# 05-Power_A.net
KiCad netlist of a schematic drawn in Altium Designer
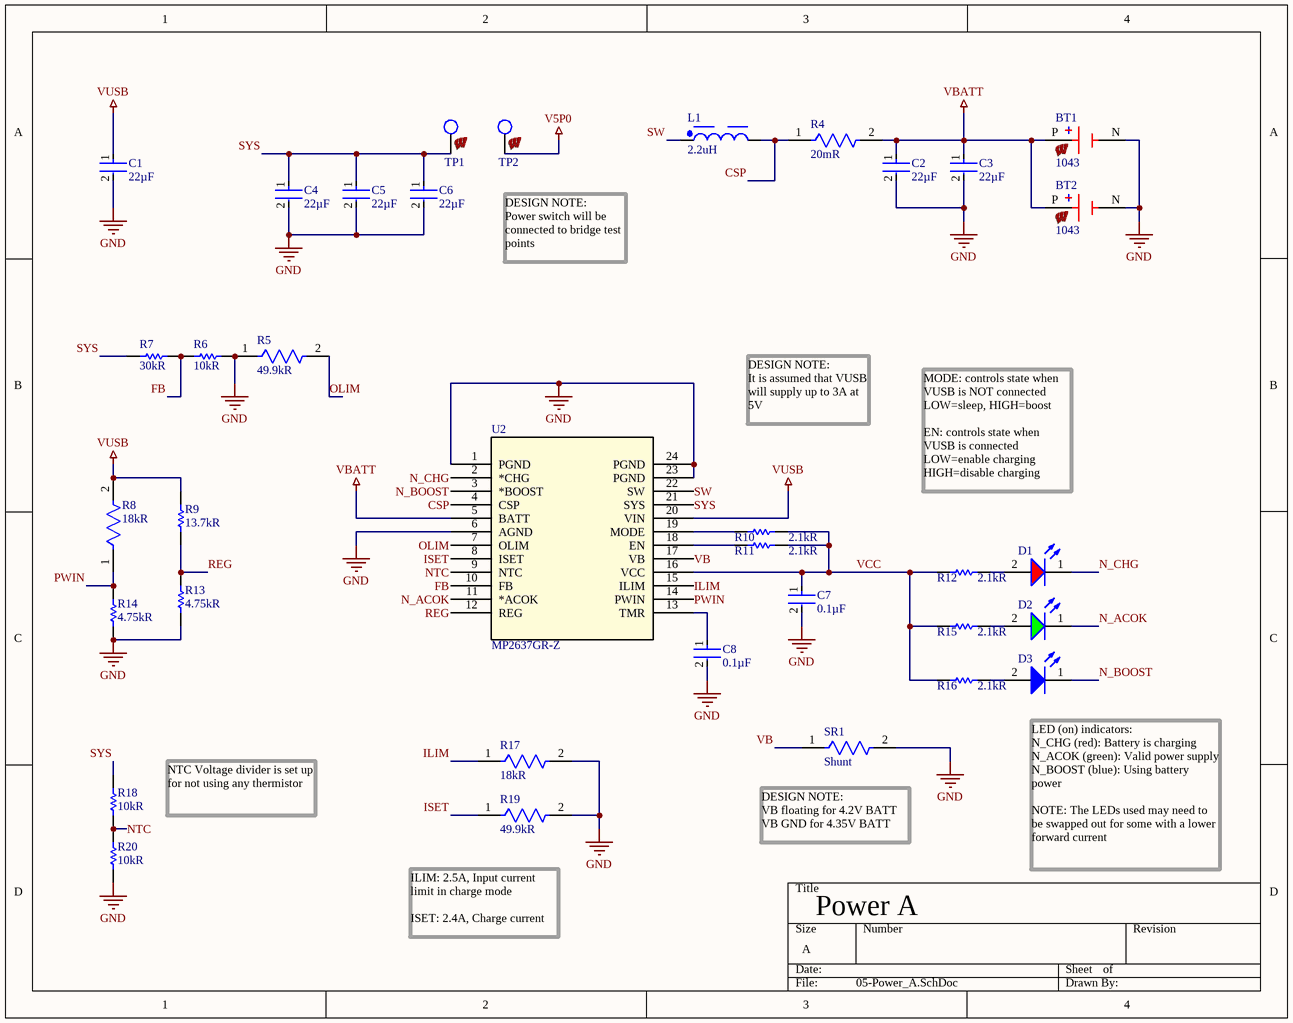
[diagram p0: 05-Power_A.SchDoc]

(export (version "E")
  (design (tool "Eeschema 10.0.6"))
  (components
    (comp (ref "BT1")
      (value "1043")
      (footprint "BAT_1043")
      (fields (field (name "MANUFACTURER") "Keystone Electronics"))
      (libsource (lib "uw-madison-parts") (part "1043"))
    )
    (comp (ref "BT2")
      (value "1043")
      (footprint "BAT_1043")
      (fields (field (name "MANUFACTURER") "Keystone Electronics"))
      (libsource (lib "uw-madison-parts") (part "1043"))
    )
    (comp (ref "C1")
      (value "22µF")
      (footprint "FP-GRM21B-0_2-e0_2_0_7-IPC_B")
      (description "Chip Multilayer Ceramic Capacitors for General Purpose, 0805, 22uF, X7R, 15%, 20%, 10V")
      (libsource (lib "Altium Content Vault") (part "b4654b650e69147ec39a6b967a45e02"))
    )
    (comp (ref "C2")
      (value "22µF")
      (footprint "FP-GRM21B-0_2-e0_2_0_7-IPC_B")
      (description "Chip Multilayer Ceramic Capacitors for General Purpose, 0805, 22uF, X7R, 15%, 20%, 10V")
      (libsource (lib "Altium Content Vault") (part "b4654b650e69147ec39a6b967a45e02"))
    )
    (comp (ref "C3")
      (value "22µF")
      (footprint "FP-GRM21B-0_2-e0_2_0_7-IPC_B")
      (description "Chip Multilayer Ceramic Capacitors for General Purpose, 0805, 22uF, X7R, 15%, 20%, 10V")
      (libsource (lib "Altium Content Vault") (part "b4654b650e69147ec39a6b967a45e02"))
    )
    (comp (ref "C4")
      (value "22µF")
      (footprint "FP-GRM21B-0_2-e0_2_0_7-IPC_B")
      (description "Chip Multilayer Ceramic Capacitors for General Purpose, 0805, 22uF, X7R, 15%, 20%, 10V")
      (libsource (lib "Altium Content Vault") (part "b4654b650e69147ec39a6b967a45e02"))
    )
    (comp (ref "C5")
      (value "22µF")
      (footprint "FP-GRM21B-0_2-e0_2_0_7-IPC_B")
      (description "Chip Multilayer Ceramic Capacitors for General Purpose, 0805, 22uF, X7R, 15%, 20%, 10V")
      (libsource (lib "Altium Content Vault") (part "b4654b650e69147ec39a6b967a45e02"))
    )
    (comp (ref "C6")
      (value "22µF")
      (footprint "FP-GRM21B-0_2-e0_2_0_7-IPC_B")
      (description "Chip Multilayer Ceramic Capacitors for General Purpose, 0805, 22uF, X7R, 15%, 20%, 10V")
      (libsource (lib "Altium Content Vault") (part "b4654b650e69147ec39a6b967a45e02"))
    )
    (comp (ref "C7")
      (value "0.1µF")
      (footprint "FP-C0805C-DN-MFG")
      (description "CAP CER 0.1UF 50V X7R 0805")
      (fields
        (field (name "MANUFACTURER PART NUMBER") "C0805C104K5RACTU")
        (field (name "MANUFACTURER") "KEMET")
      )
      (libsource (lib "Altium Content Vault") (part "b4654b650e69147ec39a6b967a45e02"))
    )
    (comp (ref "C8")
      (value "0.1µF")
      (footprint "FP-C0805C-DN-MFG")
      (description "CAP CER 0.1UF 50V X7R 0805")
      (fields
        (field (name "MANUFACTURER PART NUMBER") "C0805C104K5RACTU")
        (field (name "MANUFACTURER") "KEMET")
      )
      (libsource (lib "Altium Content Vault") (part "b4654b650e69147ec39a6b967a45e02"))
    )
    (comp (ref "D1")
      (value "150080RS75000")
      (footprint "WL-SMCW_0805_150080xx75000")
      (description "150080RS75000\r\nLED Uni-Color Red 630nm 2-Pin Chip 0805(2012Metric) T/R")
      (libsource (lib "Altium Content Vault") (part "LED_Red_2A-1K"))
    )
    (comp (ref "D2")
      (value "150080GS75000")
      (footprint "WL-SMCW_0805_150080xx75000")
      (description "WURTH ELEKTRONIK - 150080GS75000 - LED, Green, SMD, 0805, 30 mA, 3.2 V, 520 nm")
      (libsource (lib "Altium Content Vault") (part "LED_Green_2A-1K"))
    )
    (comp (ref "D3")
      (value "150080BS75000")
      (footprint "WL-SMCW_0805_150080xx75000")
      (description "Led, Blue, 470 Nm, 3.2 V, 30 Ma, 145 Mcd Rohs Compliant: Yes")
      (libsource (lib "Altium Content Vault") (part "LED_Blue_2A-1K"))
    )
    (comp (ref "L1")
      (value "2.2uH")
      (footprint "WE-TPC_8043")
      (description "Fixed Ind 2.2UH 5.4A 13 Mohm SMD")
      (fields (field (name "TOLERANCE") "30%"))
      (libsource (lib "Altium Content Vault") (part "Inductor - 2"))
    )
    (comp (ref "R4")
      (value "20mR")
      (footprint "FP-CSR0805-MFG")
      (description "General Purpose Thick Film Chip Resistor, 0805, 20mΩ, 1%, 200ppm/°C, 0.25W")
      (fields (field (name "TOLERANCE") "1%"))
      (libsource (lib "Altium Content Vault") (part "1029c3af85768c4190bb7ad29bc67b5"))
    )
    (comp (ref "R5")
      (value "49.9kR")
      (footprint "FP-RMCF0805-IPC_A")
      (description "49.9kΩ ±1% 0.125W 0805 Thick Film Chip Resistor AEC-Q200 compliant")
      (fields (field (name "TOLERANCE") "1%"))
      (libsource (lib "Altium Content Vault") (part "1029c3af85768c4190bb7ad29bc67b5"))
    )
    (comp (ref "R6")
      (value "10kR")
      (footprint "RESC2013X70X40ML20T20")
      (fields (field (name "MANUFACTURER") "Panasonic") (field (name "PART NUMBER") "ERJ-6ENF1002V"))
      (libsource (lib "Altium Content Vault") (part "RES"))
    )
    (comp (ref "R7")
      (value "30kR")
      (footprint "RESC2013X70X40LL20T20")
      (description "RES 30.0K OHM 1/8W 1% 0805 SMD")
      (fields (field (name "MANUFACTURER") "Panasonic") (field (name "PARTNUMBER") "ERJ-6ENF3002V"))
      (libsource (lib "Altium Content Vault") (part "RES-2"))
    )
    (comp (ref "R8")
      (value "18kR")
      (footprint "FP-CRGP0805-IPC_C")
      (description "CRGP0805 18KΩ 0.33W ±100ppm/°C 1% 150V")
      (fields
        (field (name "MANUFACTURER PART NUMBER") "CRGP0805F18K")
        (field (name "OCTOPART") "https://octopart.com/crgp0805f18k-te+connectivity-91018794")
      )
      (libsource (lib "Altium Content Vault") (part "1029c3af85768c4190bb7ad29bc67b5"))
    )
    (comp (ref "R9")
      (value "13.7kR")
      (footprint "RESC2013X70X40ML20T20")
      (description "ERJ-6ENF1372V")
      (fields (field (name "MANUFACTURER") "Panasonic"))
      (libsource (lib "Altium Content Vault") (part "RES"))
    )
    (comp (ref "R10")
      (value "2.1kR")
      (footprint "RESC2013X70X40ML20T20")
      (description "Res Thick Film 0805 2.1K Ohm 1% 0.125W(1/8W) ±100ppm/C Pad SMD T/R Automotive AEC-Q200")
      (fields (field (name "PART NUMBER") "ERJ-6ENF2101V") (field (name "MANUFACTURER") "Panasonic"))
      (libsource (lib "Altium Content Vault") (part "RES"))
    )
    (comp (ref "R11")
      (value "2.1kR")
      (footprint "RESC2013X70X40ML20T20")
      (description "Res Thick Film 0805 2.1K Ohm 1% 0.125W(1/8W) ±100ppm/C Pad SMD T/R Automotive AEC-Q200")
      (fields (field (name "PART NUMBER") "ERJ-6ENF2101V") (field (name "MANUFACTURER") "Panasonic"))
      (libsource (lib "Altium Content Vault") (part "RES"))
    )
    (comp (ref "R12")
      (value "2.1kR")
      (footprint "RESC2013X70X40ML20T20")
      (description "Res Thick Film 0805 2.1K Ohm 1% 0.125W(1/8W) ±100ppm/C Pad SMD T/R Automotive AEC-Q200")
      (fields (field (name "PART NUMBER") "ERJ-6ENF2101V") (field (name "MANUFACTURER") "Panasonic"))
      (libsource (lib "Altium Content Vault") (part "RES"))
    )
    (comp (ref "R13")
      (value "4.75kR")
      (footprint "RESC2013X50X30LL20T20")
      (description "CRCW08054K75FKTA")
      (fields (field (name "MANUFACTURER") "Vishay Dale"))
      (libsource (lib "Altium Content Vault") (part "RES"))
    )
    (comp (ref "R14")
      (value "4.75kR")
      (footprint "RESC2013X50X30LL20T20")
      (description "CRCW08054K75FKTA")
      (fields (field (name "MANUFACTURER") "Vishay Dale"))
      (libsource (lib "Altium Content Vault") (part "RES"))
    )
    (comp (ref "R15")
      (value "2.1kR")
      (footprint "RESC2013X70X40ML20T20")
      (description "Res Thick Film 0805 2.1K Ohm 1% 0.125W(1/8W) ±100ppm/C Pad SMD T/R Automotive AEC-Q200")
      (fields (field (name "PART NUMBER") "ERJ-6ENF2101V") (field (name "MANUFACTURER") "Panasonic"))
      (libsource (lib "Altium Content Vault") (part "RES"))
    )
    (comp (ref "R16")
      (value "2.1kR")
      (footprint "RESC2013X70X40ML20T20")
      (description "Res Thick Film 0805 2.1K Ohm 1% 0.125W(1/8W) ±100ppm/C Pad SMD T/R Automotive AEC-Q200")
      (fields (field (name "PART NUMBER") "ERJ-6ENF2101V") (field (name "MANUFACTURER") "Panasonic"))
      (libsource (lib "Altium Content Vault") (part "RES"))
    )
    (comp (ref "R17")
      (value "18kR")
      (footprint "FP-CRGP0805-IPC_C")
      (description "CRGP0805 18KΩ 0.33W ±100ppm/°C 1% 150V")
      (fields
        (field (name "MANUFACTURER PART NUMBER") "CRGP0805F18K")
        (field (name "OCTOPART") "https://octopart.com/crgp0805f18k-te+connectivity-91018794")
      )
      (libsource (lib "Altium Content Vault") (part "1029c3af85768c4190bb7ad29bc67b5"))
    )
    (comp (ref "R18")
      (value "10kR")
      (footprint "RESC2013X70X40ML20T20")
      (fields (field (name "MANUFACTURER") "Panasonic") (field (name "PART NUMBER") "ERJ-6ENF1002V"))
      (libsource (lib "Altium Content Vault") (part "RES"))
    )
    (comp (ref "R19")
      (value "49.9kR")
      (footprint "FP-RMCF0805-IPC_A")
      (description "49.9kΩ ±1% 0.125W 0805 Thick Film Chip Resistor AEC-Q200 compliant")
      (fields (field (name "TOLERANCE") "1%"))
      (libsource (lib "Altium Content Vault") (part "1029c3af85768c4190bb7ad29bc67b5"))
    )
    (comp (ref "R20")
      (value "10kR")
      (footprint "RESC2013X70X40ML20T20")
      (fields (field (name "MANUFACTURER") "Panasonic") (field (name "PART NUMBER") "ERJ-6ENF1002V"))
      (libsource (lib "Altium Content Vault") (part "RES"))
    )
    (comp (ref "SR1")
      (value "Shunt")
      (footprint "FP-CSSH0805FT1L00-MFG")
      (description "CSSH0805FT1L00\r\nRES SHUNT, 0805, 0.001 OHM, 1%,")
      (libsource (lib "Altium Content Vault") (part "1029c3af85768c4190bb7ad29bc67b5"))
    )
    (comp (ref "TP1")
      (value "TP")
      (footprint "TP_UW")
      (description "Power switch source terminal.\r\nDebugging Test Point 0.3/0.6mm")
      (libsource (lib "uw-madison-parts") (part "TP"))
    )
    (comp (ref "TP2")
      (value "TP")
      (footprint "TP_UW")
      (description "Power switch output terminal.\r\nDebugging Test Point 0.3/0.6mm")
      (libsource (lib "uw-madison-parts") (part "TP"))
    )
    (comp (ref "U2")
      (value "MP2637GR-Z")
      (footprint "QFN-24_MP2637_MNP")
      (fields (field (name "COPYRIGHT") "Copyright (C) 2025 Ultra Librarian. All rights reserved."))
      (libsource (lib "MP2637GR-Z") (part "MP2637GR-Z"))
    )
  )
  (nets
    (net (code "1") (name "/CSP") (class "Default")
      (node (ref "L1") (pin "2") (pinfunction "2_2") (pintype "passive"))
      (node (ref "R4") (pin "1") (pinfunction "1_1") (pintype "passive"))
      (node (ref "U2") (pin "4") (pinfunction "CSP_4") (pintype "passive"))
    )
    (net (code "2") (name "/FB") (class "Default")
      (node (ref "R6") (pin "1") (pinfunction "1_1") (pintype "passive"))
      (node (ref "R7") (pin "2") (pinfunction "2_2") (pintype "passive"))
      (node (ref "U2") (pin "10") (pinfunction "FB_10") (pintype "passive"))
    )
    (net (code "3") (name "/ILIM") (class "Default")
      (node (ref "R17") (pin "1") (pinfunction "1_1") (pintype "passive"))
      (node (ref "U2") (pin "15") (pinfunction "ILIM_15") (pintype "passive"))
    )
    (net (code "4") (name "/ISET") (class "Default")
      (node (ref "R19") (pin "1") (pinfunction "1_1") (pintype "passive"))
      (node (ref "U2") (pin "8") (pinfunction "ISET_8") (pintype "passive"))
    )
    (net (code "5") (name "/NTC") (class "Default")
      (node (ref "R18") (pin "1") (pinfunction "1_1") (pintype "passive"))
      (node (ref "R20") (pin "2") (pinfunction "2_2") (pintype "passive"))
      (node (ref "U2") (pin "9") (pinfunction "NTC_9") (pintype "passive"))
    )
    (net (code "6") (name "/N_ACOK") (class "Default")
      (node (ref "D2") (pin "1") (pinfunction "K_1") (pintype "passive"))
      (node (ref "U2") (pin "11") (pinfunction "*ACOK_11") (pintype "passive"))
    )
    (net (code "7") (name "/N_BOOST") (class "Default")
      (node (ref "D3") (pin "1") (pinfunction "K_1") (pintype "passive"))
      (node (ref "U2") (pin "3") (pinfunction "*BOOST_3") (pintype "passive"))
    )
    (net (code "8") (name "/N_CHG") (class "Default")
      (node (ref "D1") (pin "1") (pinfunction "K_1") (pintype "passive"))
      (node (ref "U2") (pin "2") (pinfunction "*CHG_2") (pintype "passive"))
    )
    (net (code "9") (name "/OLIM") (class "Default")
      (node (ref "R5") (pin "2") (pinfunction "2_2") (pintype "passive"))
      (node (ref "U2") (pin "7") (pinfunction "OLIM_7") (pintype "passive"))
    )
    (net (code "10") (name "/PWIN") (class "Default")
      (node (ref "R14") (pin "2") (pinfunction "2_2") (pintype "passive"))
      (node (ref "R8") (pin "1") (pinfunction "1_1") (pintype "passive"))
      (node (ref "U2") (pin "14") (pinfunction "PWIN_14") (pintype "passive"))
    )
    (net (code "11") (name "/REG") (class "Default")
      (node (ref "R13") (pin "2") (pinfunction "2_2") (pintype "passive"))
      (node (ref "R9") (pin "1") (pinfunction "1_1") (pintype "passive"))
      (node (ref "U2") (pin "12") (pinfunction "REG_12") (pintype "passive"))
    )
    (net (code "12") (name "/SW") (class "Default")
      (node (ref "L1") (pin "1") (pinfunction "1_1") (pintype "passive"))
      (node (ref "U2") (pin "22") (pinfunction "SW_22") (pintype "passive"))
    )
    (net (code "13") (name "/SYS") (class "Default")
      (node (ref "C4") (pin "1") (pinfunction "1_1") (pintype "passive"))
      (node (ref "C5") (pin "1") (pinfunction "1_1") (pintype "passive"))
      (node (ref "C6") (pin "1") (pinfunction "1_1") (pintype "passive"))
      (node (ref "R18") (pin "2") (pinfunction "2_2") (pintype "passive"))
      (node (ref "R7") (pin "1") (pinfunction "1_1") (pintype "passive"))
      (node (ref "TP1") (pin "1") (pintype "passive"))
      (node (ref "U2") (pin "21") (pinfunction "SYS_21") (pintype "passive"))
    )
    (net (code "14") (name "/VB") (class "Default")
      (node (ref "SR1") (pin "1") (pinfunction "1_1") (pintype "passive"))
      (node (ref "U2") (pin "17") (pinfunction "VB_17") (pintype "passive"))
    )
    (net (code "15") (name "/VCC") (class "Default")
      (node (ref "C7") (pin "1") (pinfunction "1_1") (pintype "passive"))
      (node (ref "R10") (pin "2") (pinfunction "2_2") (pintype "passive"))
      (node (ref "R11") (pin "2") (pinfunction "2_2") (pintype "passive"))
      (node (ref "R12") (pin "1") (pinfunction "1_1") (pintype "passive"))
      (node (ref "R15") (pin "1") (pinfunction "1_1") (pintype "passive"))
      (node (ref "R16") (pin "1") (pinfunction "1_1") (pintype "passive"))
      (node (ref "U2") (pin "16") (pinfunction "VCC_16") (pintype "power_in"))
    )
    (net (code "16") (name "GND") (class "Default")
      (node (ref "BT1") (pin "N") (pinfunction "NEG_N") (pintype "passive"))
      (node (ref "BT2") (pin "N") (pinfunction "NEG_N") (pintype "passive"))
      (node (ref "C1") (pin "2") (pinfunction "2_2") (pintype "passive"))
      (node (ref "C2") (pin "2") (pinfunction "2_2") (pintype "passive"))
      (node (ref "C3") (pin "2") (pinfunction "2_2") (pintype "passive"))
      (node (ref "C4") (pin "2") (pinfunction "2_2") (pintype "passive"))
      (node (ref "C5") (pin "2") (pinfunction "2_2") (pintype "passive"))
      (node (ref "C6") (pin "2") (pinfunction "2_2") (pintype "passive"))
      (node (ref "C7") (pin "2") (pinfunction "2_2") (pintype "passive"))
      (node (ref "C8") (pin "2") (pinfunction "2_2") (pintype "passive"))
      (node (ref "R13") (pin "1") (pinfunction "1_1") (pintype "passive"))
      (node (ref "R14") (pin "1") (pinfunction "1_1") (pintype "passive"))
      (node (ref "R17") (pin "2") (pinfunction "2_2") (pintype "passive"))
      (node (ref "R19") (pin "2") (pinfunction "2_2") (pintype "passive"))
      (node (ref "R20") (pin "1") (pinfunction "1_1") (pintype "passive"))
      (node (ref "R5") (pin "1") (pinfunction "1_1") (pintype "passive"))
      (node (ref "R6") (pin "2") (pinfunction "2_2") (pintype "passive"))
      (node (ref "SR1") (pin "2") (pinfunction "2_2") (pintype "passive"))
      (node (ref "U2") (pin "1") (pinfunction "PGND_1") (pintype "power_in"))
      (node (ref "U2") (pin "23") (pinfunction "PGND_23") (pintype "power_in"))
      (node (ref "U2") (pin "24") (pinfunction "PGND_24") (pintype "power_in"))
      (node (ref "U2") (pin "6") (pinfunction "AGND_6") (pintype "power_in"))
    )
    (net (code "17") (name "Net-(D1-A)") (class "Default")
      (node (ref "D1") (pin "2") (pinfunction "A_2") (pintype "passive"))
      (node (ref "R12") (pin "2") (pinfunction "2_2") (pintype "passive"))
    )
    (net (code "18") (name "Net-(D2-A)") (class "Default")
      (node (ref "D2") (pin "2") (pinfunction "A_2") (pintype "passive"))
      (node (ref "R15") (pin "2") (pinfunction "2_2") (pintype "passive"))
    )
    (net (code "19") (name "Net-(D3-A)") (class "Default")
      (node (ref "D3") (pin "2") (pinfunction "A_2") (pintype "passive"))
      (node (ref "R16") (pin "2") (pinfunction "2_2") (pintype "passive"))
    )
    (net (code "20") (name "Net-(U2-EN)") (class "Default")
      (node (ref "R11") (pin "1") (pinfunction "1_1") (pintype "passive"))
      (node (ref "U2") (pin "18") (pinfunction "EN_18") (pintype "passive"))
    )
    (net (code "21") (name "Net-(U2-MODE)") (class "Default")
      (node (ref "R10") (pin "1") (pinfunction "1_1") (pintype "passive"))
      (node (ref "U2") (pin "19") (pinfunction "MODE_19") (pintype "passive"))
    )
    (net (code "22") (name "Net-(U2-TMR)") (class "Default")
      (node (ref "C8") (pin "1") (pinfunction "1_1") (pintype "passive"))
      (node (ref "U2") (pin "13") (pinfunction "TMR_13") (pintype "passive"))
    )
    (net (code "23") (name "V5P0") (class "Default") (node (ref "TP2") (pin "1") (pintype "passive")))
    (net (code "24") (name "VBATT") (class "Default")
      (node (ref "BT1") (pin "P") (pinfunction "POS_P") (pintype "passive"))
      (node (ref "BT2") (pin "P") (pinfunction "POS_P") (pintype "passive"))
      (node (ref "C2") (pin "1") (pinfunction "1_1") (pintype "passive"))
      (node (ref "C3") (pin "1") (pinfunction "1_1") (pintype "passive"))
      (node (ref "R4") (pin "2") (pinfunction "2_2") (pintype "passive"))
      (node (ref "U2") (pin "5") (pinfunction "BATT_5") (pintype "passive"))
    )
    (net (code "25") (name "VUSB") (class "Default")
      (node (ref "C1") (pin "1") (pinfunction "1_1") (pintype "passive"))
      (node (ref "R8") (pin "2") (pinfunction "2_2") (pintype "passive"))
      (node (ref "R9") (pin "2") (pinfunction "2_2") (pintype "passive"))
      (node (ref "U2") (pin "20") (pinfunction "VIN_20") (pintype "power_in"))
    )
  )
)
